# DC075B_INPUT_CLOCKS.net
KiCad netlist of a schematic drawn in Altium Designer
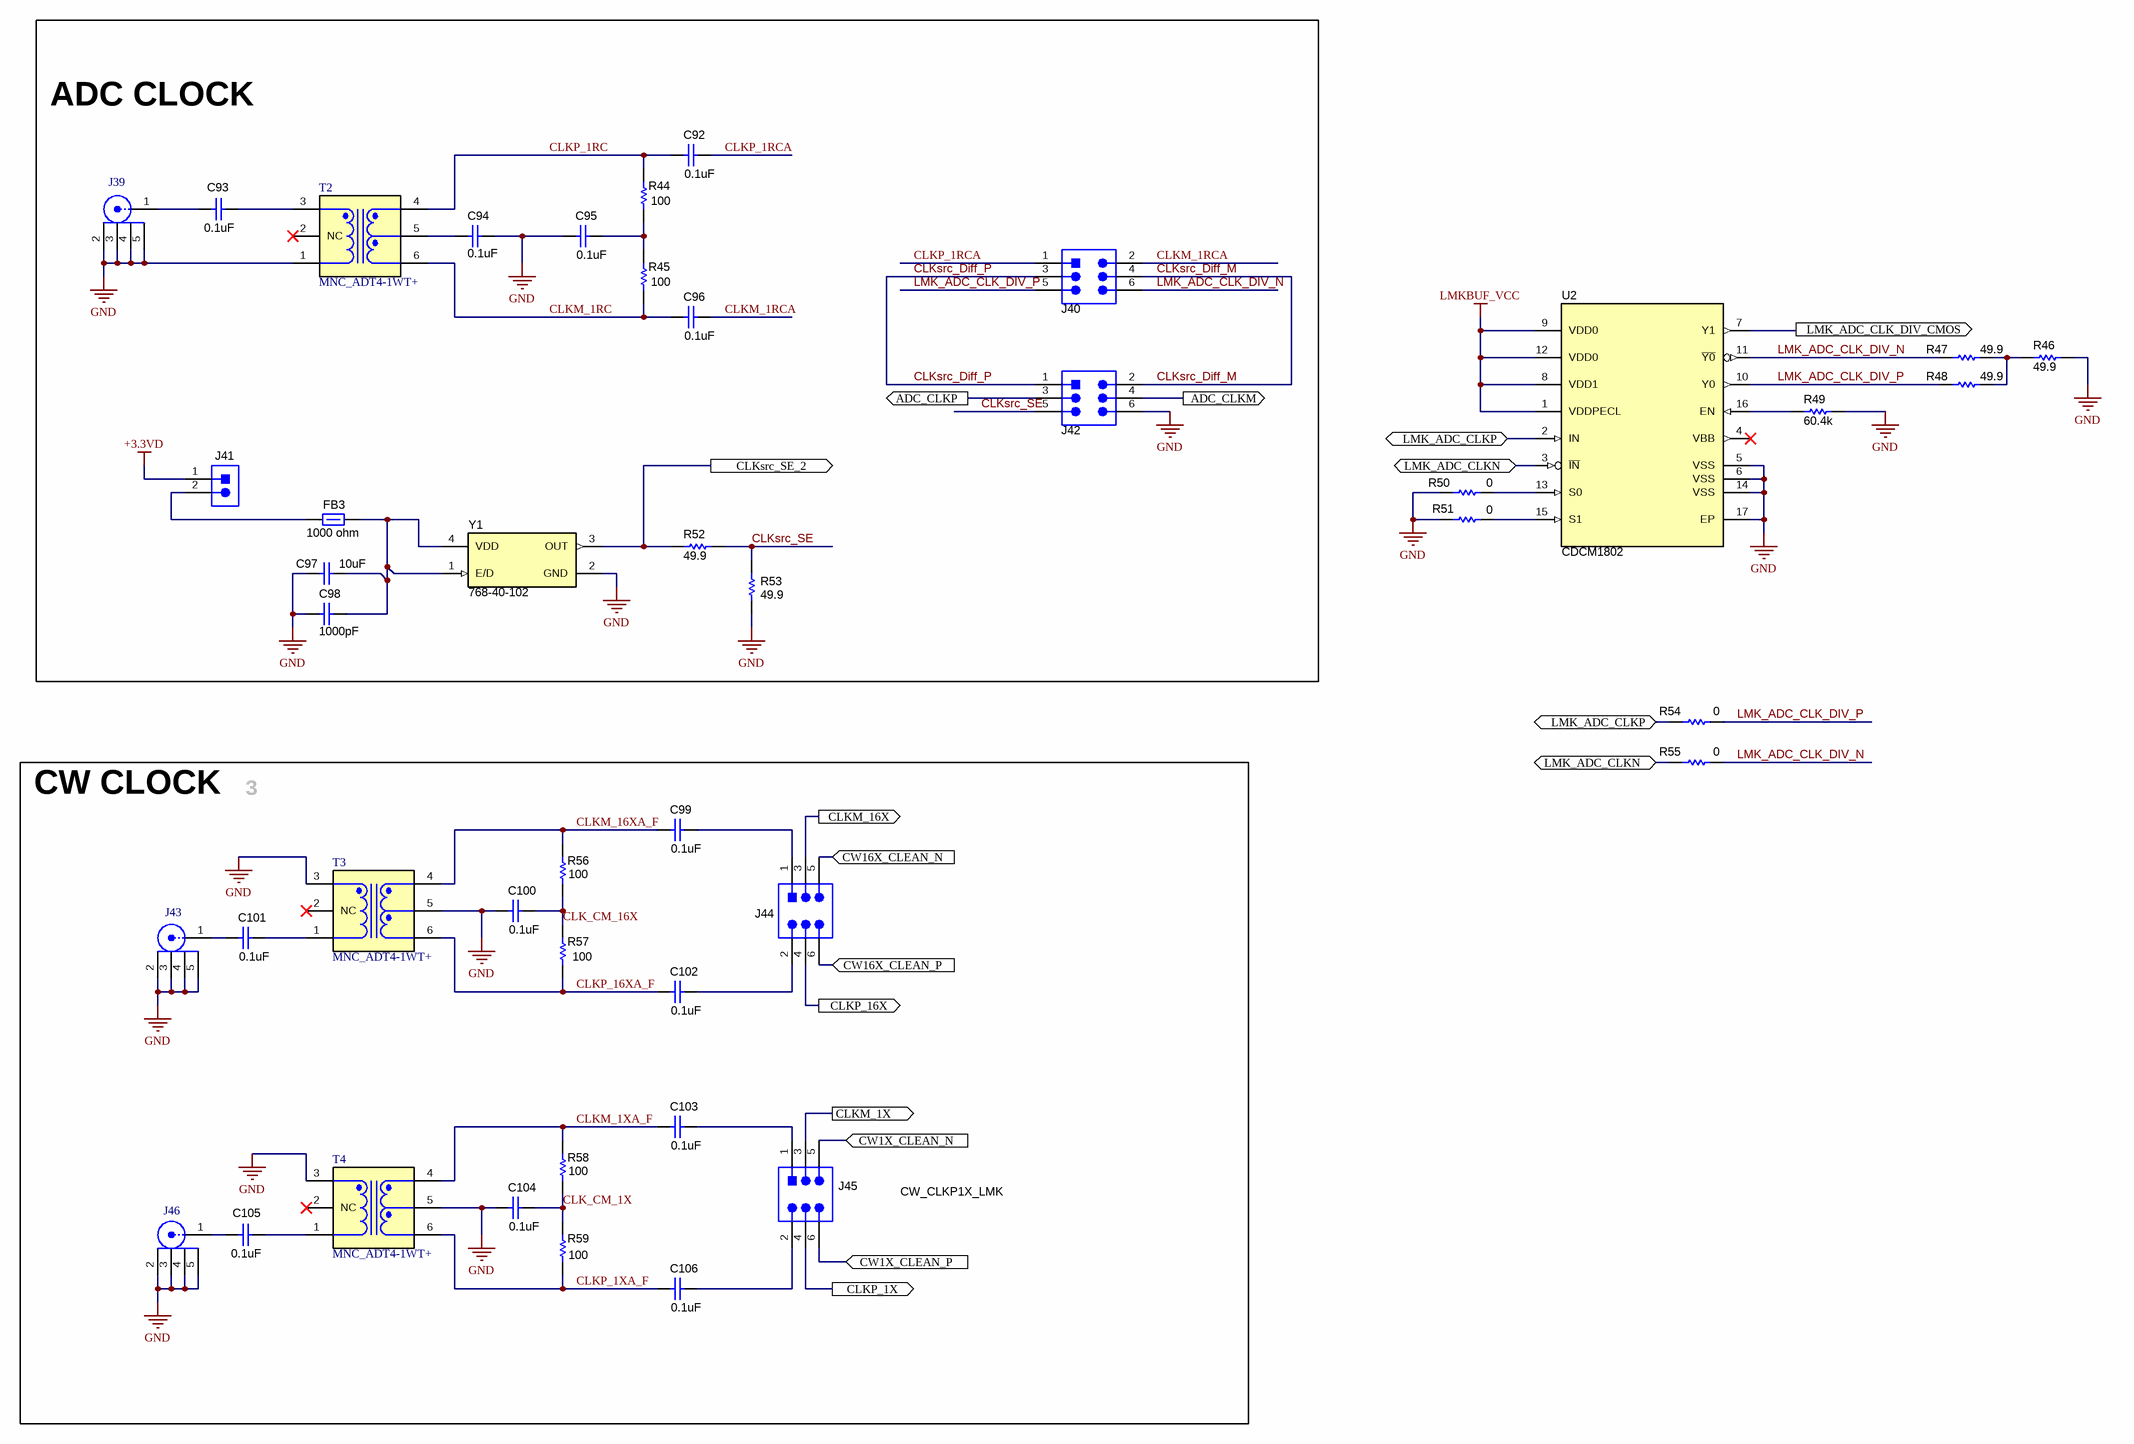
[diagram p0: DC075B_INPUT_CLOCKS.SchDoc]

(export (version "E")
  (design (tool "Eeschema 10.0.6"))
  (components
    (comp (ref "C92")
      (value "0.1uF")
      (footprint "0402")
      (description "CAP, CERM, 0.1 uF, 16 V, +/- 10%, X7R, 0402")
      (fields
        (field (name "PARTNUMBER") "GRM155R71C104KA88D")
        (field (name "MANUFACTURER") "MuRata")
        (field (name "PUBLISHER") "Texas Instruments")
      )
      (libsource (lib "Altium Vault - TI") (part "Capacitor"))
    )
    (comp (ref "C93")
      (value "0.1uF")
      (footprint "0402")
      (description "CAP, CERM, 0.1 uF, 16 V, +/- 10%, X7R, 0402")
      (fields
        (field (name "PARTNUMBER") "GRM155R71C104KA88D")
        (field (name "MANUFACTURER") "MuRata")
        (field (name "PUBLISHER") "Texas Instruments")
      )
      (libsource (lib "Altium Vault - TI") (part "Capacitor"))
    )
    (comp (ref "C94")
      (value "0.1uF")
      (footprint "0402")
      (description "CAP, CERM, 0.1 uF, 16 V, +/- 10%, X7R, 0402")
      (fields
        (field (name "PARTNUMBER") "GRM155R71C104KA88D")
        (field (name "MANUFACTURER") "MuRata")
        (field (name "PUBLISHER") "Texas Instruments")
      )
      (libsource (lib "Altium Vault - TI") (part "Capacitor"))
    )
    (comp (ref "C95")
      (value "0.1uF")
      (footprint "0402")
      (description "CAP, CERM, 0.1 uF, 16 V, +/- 10%, X7R, 0402")
      (fields
        (field (name "PARTNUMBER") "GRM155R71C104KA88D")
        (field (name "MANUFACTURER") "MuRata")
        (field (name "PUBLISHER") "Texas Instruments")
      )
      (libsource (lib "Altium Vault - TI") (part "Capacitor"))
    )
    (comp (ref "C96")
      (value "0.1uF")
      (footprint "0402")
      (description "CAP, CERM, 0.1 uF, 16 V, +/- 10%, X7R, 0402")
      (fields
        (field (name "PARTNUMBER") "GRM155R71C104KA88D")
        (field (name "MANUFACTURER") "MuRata")
        (field (name "PUBLISHER") "Texas Instruments")
      )
      (libsource (lib "Altium Vault - TI") (part "Capacitor"))
    )
    (comp (ref "C97")
      (value "10uF")
      (footprint "0603_HV")
      (description "CAP, CERM, 10 uF, 6.3 V, +/- 20%, X5R, 0603")
      (fields
        (field (name "PARTNUMBER") "C0603C106M9PACTU")
        (field (name "MANUFACTURER") "Kemet")
        (field (name "PUBLISHER") "Texas Instruments")
      )
      (libsource (lib "Altium Vault - TI") (part "Capacitor"))
    )
    (comp (ref "C98")
      (value "885012205044")
      (footprint "0402")
      (description "CAP, CERM, 1000 pF, 25 V, +/- 10%, X7R, 0402")
      (fields
        (field (name "MANUFACTURER") "Wurth Elektronik")
        (field (name "VALUEDISPLAYED") "1000pF")
        (field (name "PUBLISHER") "Texas Instruments")
      )
      (libsource (lib "Altium Vault - TI") (part "CMP-0006229-2"))
    )
    (comp (ref "C99")
      (value "0.1uF")
      (footprint "0402")
      (description "CAP, CERM, 0.1 uF, 16 V, +/- 10%, X7R, 0402")
      (fields
        (field (name "PARTNUMBER") "GRM155R71C104KA88D")
        (field (name "MANUFACTURER") "MuRata")
        (field (name "PUBLISHER") "Texas Instruments")
      )
      (libsource (lib "Altium Vault - TI") (part "Capacitor"))
    )
    (comp (ref "C100")
      (value "0.1uF")
      (footprint "0402")
      (description "CAP, CERM, 0.1 uF, 16 V, +/- 10%, X7R, 0402")
      (fields
        (field (name "PARTNUMBER") "GRM155R71C104KA88D")
        (field (name "MANUFACTURER") "MuRata")
        (field (name "PUBLISHER") "Texas Instruments")
      )
      (libsource (lib "Altium Vault - TI") (part "Capacitor"))
    )
    (comp (ref "C101")
      (value "0.1uF")
      (footprint "0402")
      (description "CAP, CERM, 0.1 uF, 16 V, +/- 10%, X7R, 0402")
      (fields
        (field (name "PARTNUMBER") "GRM155R71C104KA88D")
        (field (name "MANUFACTURER") "MuRata")
        (field (name "PUBLISHER") "Texas Instruments")
      )
      (libsource (lib "Altium Vault - TI") (part "Capacitor"))
    )
    (comp (ref "C102")
      (value "0.1uF")
      (footprint "0402")
      (description "CAP, CERM, 0.1 uF, 16 V, +/- 10%, X7R, 0402")
      (fields
        (field (name "PARTNUMBER") "GRM155R71C104KA88D")
        (field (name "MANUFACTURER") "MuRata")
        (field (name "PUBLISHER") "Texas Instruments")
      )
      (libsource (lib "Altium Vault - TI") (part "Capacitor"))
    )
    (comp (ref "C103")
      (value "0.1uF")
      (footprint "0402")
      (description "CAP, CERM, 0.1 uF, 16 V, +/- 10%, X7R, 0402")
      (fields
        (field (name "PARTNUMBER") "GRM155R71C104KA88D")
        (field (name "MANUFACTURER") "MuRata")
        (field (name "PUBLISHER") "Texas Instruments")
      )
      (libsource (lib "Altium Vault - TI") (part "Capacitor"))
    )
    (comp (ref "C104")
      (value "0.1uF")
      (footprint "0402")
      (description "CAP, CERM, 0.1 uF, 16 V, +/- 10%, X7R, 0402")
      (fields
        (field (name "PARTNUMBER") "GRM155R71C104KA88D")
        (field (name "MANUFACTURER") "MuRata")
        (field (name "PUBLISHER") "Texas Instruments")
      )
      (libsource (lib "Altium Vault - TI") (part "Capacitor"))
    )
    (comp (ref "C105")
      (value "0.1uF")
      (footprint "0402")
      (description "CAP, CERM, 0.1 uF, 16 V, +/- 10%, X7R, 0402")
      (fields
        (field (name "PARTNUMBER") "GRM155R71C104KA88D")
        (field (name "MANUFACTURER") "MuRata")
        (field (name "PUBLISHER") "Texas Instruments")
      )
      (libsource (lib "Altium Vault - TI") (part "Capacitor"))
    )
    (comp (ref "C106")
      (value "0.1uF")
      (footprint "0402")
      (description "CAP, CERM, 0.1 uF, 16 V, +/- 10%, X7R, 0402")
      (fields
        (field (name "PARTNUMBER") "GRM155R71C104KA88D")
        (field (name "MANUFACTURER") "MuRata")
        (field (name "PUBLISHER") "Texas Instruments")
      )
      (libsource (lib "Altium Vault - TI") (part "Capacitor"))
    )
    (comp (ref "FB3")
      (value "1000 ohm")
      (footprint "0402")
      (description "Ferrite Bead, 1000 ohm @ 100 MHz, 0.3 A, 0402")
      (fields
        (field (name "PARTNUMBER") "BLM15AG102SN1D")
        (field (name "MANUFACTURER") "MuRata")
        (field (name "PUBLISHER") "Texas Instruments")
      )
      (libsource (lib "Altium Vault - TI") (part "Ferrite_Bead"))
    )
    (comp (ref "J39")
      (value "5-1814832-1")
      (footprint "TE_5-1814832-1")
      (description "SMA Straight PCB Socket Die Cast, 50 Ohm, TH")
      (fields (field (name "MANUFACTURER") "TE Connectivity") (field (name "PUBLISHER") "Texas Instruments"))
      (libsource (lib "Altium Vault - TI") (part "SMA_Contact1_GND2345"))
    )
    (comp (ref "J40")
      (value "Header_3x2")
      (footprint "TSW-103-07-G-D")
      (description "Header, 100mil, 3x2, Gold, TH")
      (fields (field (name "PARTNUMBER") "TSW-103-07-G-D") (field (name "MANUFACTURER") "Samtec"))
      (libsource (lib "Altium Vault - TI") (part "Header_3x2"))
    )
    (comp (ref "J41")
      (value "Header_2x1")
      (footprint "TSW-102-07-G-S")
      (description "Header, 100mil, 2x1, Gold, TH")
      (fields (field (name "PARTNUMBER") "TSW-102-07-G-S") (field (name "MANUFACTURER") "Samtec"))
      (libsource (lib "Altium Vault - TI") (part "Header_2x1"))
    )
    (comp (ref "J42")
      (value "Header_3x2")
      (footprint "TSW-103-07-G-D")
      (description "Header, 100mil, 3x2, Gold, TH")
      (fields (field (name "PARTNUMBER") "TSW-103-07-G-D") (field (name "MANUFACTURER") "Samtec"))
      (libsource (lib "Altium Vault - TI") (part "Header_3x2"))
    )
    (comp (ref "J43")
      (value "5-1814832-1")
      (footprint "TE_5-1814832-1")
      (description "SMA Straight PCB Socket Die Cast, 50 Ohm, TH")
      (fields (field (name "MANUFACTURER") "TE Connectivity") (field (name "PUBLISHER") "Texas Instruments"))
      (libsource (lib "Altium Vault - TI") (part "SMA_Contact1_GND2345"))
    )
    (comp (ref "J44")
      (value "Header_3x2")
      (footprint "TSW-103-07-G-D")
      (description "Header, 100mil, 3x2, Gold, TH")
      (fields (field (name "PARTNUMBER") "TSW-103-07-G-D") (field (name "MANUFACTURER") "Samtec"))
      (libsource (lib "") (part "Header_3x2_1"))
    )
    (comp (ref "J45")
      (value "Header_3x2")
      (footprint "TSW-103-07-G-D")
      (description "Header, 100mil, 3x2, Gold, TH")
      (fields (field (name "PARTNUMBER") "TSW-103-07-G-D") (field (name "MANUFACTURER") "Samtec"))
      (libsource (lib "") (part "Header_3x2_1"))
    )
    (comp (ref "J46")
      (value "5-1814832-1")
      (footprint "TE_5-1814832-1")
      (description "SMA Straight PCB Socket Die Cast, 50 Ohm, TH")
      (fields (field (name "MANUFACTURER") "TE Connectivity") (field (name "PUBLISHER") "Texas Instruments"))
      (libsource (lib "Altium Vault - TI") (part "SMA_Contact1_GND2345"))
    )
    (comp (ref "R44")
      (value "Resistor")
      (footprint "0402")
      (description "RES, 100, 1%, 0.1 W, 0402")
      (fields
        (field (name "MANUFACTURER") "Panasonic")
        (field (name "PARTNUMBER") "ERJ-2RKF1000X")
        (field (name "VALUEDISPLAYED") "100")
        (field (name "PUBLISHER") "Texas Instruments")
      )
      (libsource (lib "Altium Vault - TI") (part "Resistor"))
    )
    (comp (ref "R45")
      (value "Resistor")
      (footprint "0402")
      (description "RES, 100, 1%, 0.1 W, 0402")
      (fields
        (field (name "MANUFACTURER") "Panasonic")
        (field (name "PARTNUMBER") "ERJ-2RKF1000X")
        (field (name "VALUEDISPLAYED") "100")
        (field (name "PUBLISHER") "Texas Instruments")
      )
      (libsource (lib "Altium Vault - TI") (part "Resistor"))
    )
    (comp (ref "R46")
      (value "49.9")
      (footprint "0402")
      (description "RES, 49.9, 1%, 0.063 W, AEC-Q200 Grade 0, 0402")
      (fields (field (name "MANUFACTURER") "Vishay-Dale") (field (name "PARTNUMBER") "CRCW040249R9FKED"))
      (libsource (lib "Altium Vault - TI") (part "Resistor"))
    )
    (comp (ref "R47")
      (value "49.9")
      (footprint "0402")
      (description "RES, 49.9, 1%, 0.063 W, AEC-Q200 Grade 0, 0402")
      (fields (field (name "MANUFACTURER") "Vishay-Dale") (field (name "PARTNUMBER") "CRCW040249R9FKED"))
      (libsource (lib "Altium Vault - TI") (part "Resistor"))
    )
    (comp (ref "R48")
      (value "49.9")
      (footprint "0402")
      (description "RES, 49.9, 1%, 0.063 W, AEC-Q200 Grade 0, 0402")
      (fields (field (name "MANUFACTURER") "Vishay-Dale") (field (name "PARTNUMBER") "CRCW040249R9FKED"))
      (libsource (lib "Altium Vault - TI") (part "Resistor"))
    )
    (comp (ref "R49")
      (value "60.4k")
      (footprint "0402")
      (description "RES, 60.4 k, 1%, 0.063 W, AEC-Q200 Grade 0, 0402")
      (fields (field (name "PARTNUMBER") "CRCW040260K4FKED") (field (name "MANUFACTURER") "Vishay-Dale"))
      (libsource (lib "Altium Vault - TI") (part "Resistor"))
    )
    (comp (ref "R50")
      (value "0")
      (footprint "0402")
      (description "RES, 0, 5%, 0.063 W, AEC-Q200 Grade 0, 0402")
      (fields (field (name "MANUFACTURER") "Vishay-Dale") (field (name "PARTNUMBER") "CRCW04020000Z0ED"))
      (libsource (lib "Altium Vault - TI") (part "Resistor"))
    )
    (comp (ref "R51")
      (value "0")
      (footprint "0402")
      (description "RES, 0, 5%, 0.063 W, AEC-Q200 Grade 0, 0402")
      (fields (field (name "MANUFACTURER") "Vishay-Dale") (field (name "PARTNUMBER") "CRCW04020000Z0ED"))
      (libsource (lib "Altium Vault - TI") (part "Resistor"))
    )
    (comp (ref "R52")
      (value "49.9")
      (footprint "0402")
      (description "RES, 49.9, 1%, 0.063 W, AEC-Q200 Grade 0, 0402")
      (fields (field (name "MANUFACTURER") "Vishay-Dale") (field (name "PARTNUMBER") "CRCW040249R9FKED"))
      (libsource (lib "Altium Vault - TI") (part "Resistor"))
    )
    (comp (ref "R53")
      (value "49.9")
      (footprint "0402")
      (description "RES, 49.9, 1%, 0.063 W, AEC-Q200 Grade 0, 0402")
      (fields (field (name "MANUFACTURER") "Vishay-Dale") (field (name "PARTNUMBER") "CRCW040249R9FKED"))
      (libsource (lib "Altium Vault - TI") (part "Resistor"))
    )
    (comp (ref "R54")
      (value "0")
      (footprint "0402")
      (description "RES, 0, 5%, 0.063 W, AEC-Q200 Grade 0, 0402")
      (fields (field (name "MANUFACTURER") "Vishay-Dale") (field (name "PARTNUMBER") "CRCW04020000Z0ED"))
      (libsource (lib "Altium Vault - TI") (part "Resistor"))
    )
    (comp (ref "R55")
      (value "0")
      (footprint "0402")
      (description "RES, 0, 5%, 0.063 W, AEC-Q200 Grade 0, 0402")
      (fields (field (name "MANUFACTURER") "Vishay-Dale") (field (name "PARTNUMBER") "CRCW04020000Z0ED"))
      (libsource (lib "Altium Vault - TI") (part "Resistor"))
    )
    (comp (ref "R56")
      (value "Resistor")
      (footprint "0402")
      (description "RES, 100, 1%, 0.1 W, 0402")
      (fields
        (field (name "MANUFACTURER") "Panasonic")
        (field (name "PARTNUMBER") "ERJ-2RKF1000X")
        (field (name "VALUEDISPLAYED") "100")
        (field (name "PUBLISHER") "Texas Instruments")
      )
      (libsource (lib "Altium Vault - TI") (part "Resistor"))
    )
    (comp (ref "R57")
      (value "Resistor")
      (footprint "0402")
      (description "RES, 100, 1%, 0.1 W, 0402")
      (fields
        (field (name "MANUFACTURER") "Panasonic")
        (field (name "PARTNUMBER") "ERJ-2RKF1000X")
        (field (name "VALUEDISPLAYED") "100")
        (field (name "PUBLISHER") "Texas Instruments")
      )
      (libsource (lib "Altium Vault - TI") (part "Resistor"))
    )
    (comp (ref "R58")
      (value "Resistor")
      (footprint "0402")
      (description "RES, 100, 1%, 0.1 W, 0402")
      (fields
        (field (name "MANUFACTURER") "Panasonic")
        (field (name "PARTNUMBER") "ERJ-2RKF1000X")
        (field (name "VALUEDISPLAYED") "100")
        (field (name "PUBLISHER") "Texas Instruments")
      )
      (libsource (lib "Altium Vault - TI") (part "Resistor"))
    )
    (comp (ref "R59")
      (value "Resistor")
      (footprint "0402")
      (description "RES, 100, 1%, 0.1 W, 0402")
      (fields
        (field (name "MANUFACTURER") "Panasonic")
        (field (name "PARTNUMBER") "ERJ-2RKF1000X")
        (field (name "VALUEDISPLAYED") "100")
        (field (name "PUBLISHER") "Texas Instruments")
      )
      (libsource (lib "Altium Vault - TI") (part "Resistor"))
    )
    (comp (ref "T2")
      (value "MNC_ADT4-1WT+")
      (footprint "MNC_CD542")
      (description "RF Transformer, 50 ohm, 2 to 775 MHz, SMT")
      (fields
        (field (name "PARTNUMBER") "ADT4-1WT+")
        (field (name "MANUFACTURER") "Minicircuits")
        (field (name "PUBLISHER") "Texas Instruments")
      )
      (libsource (lib "Altium Vault - TI") (part "MNC_ADT4-1WT+"))
    )
    (comp (ref "T3")
      (value "MNC_ADT4-1WT+")
      (footprint "MNC_CD542")
      (description "RF Transformer, 50 ohm, 2 to 775 MHz, SMT")
      (fields
        (field (name "PARTNUMBER") "ADT4-1WT+")
        (field (name "MANUFACTURER") "Minicircuits")
        (field (name "PUBLISHER") "Texas Instruments")
      )
      (libsource (lib "Altium Vault - TI") (part "MNC_ADT4-1WT+"))
    )
    (comp (ref "T4")
      (value "MNC_ADT4-1WT+")
      (footprint "MNC_CD542")
      (description "RF Transformer, 50 ohm, 2 to 775 MHz, SMT")
      (fields
        (field (name "PARTNUMBER") "ADT4-1WT+")
        (field (name "MANUFACTURER") "Minicircuits")
        (field (name "PUBLISHER") "Texas Instruments")
      )
      (libsource (lib "Altium Vault - TI") (part "MNC_ADT4-1WT+"))
    )
    (comp (ref "U2")
      (value "CDCM1802")
      (footprint "RGT0016A")
      (description "Clock Buffer w/Programmable Divider, LVPECL I/O + addl LVCMOS output, RGT0016A (VQFN-16)")
      (fields
        (field (name "PARTNUMBER") "CDCM1802RGTR")
        (field (name "ALTERNATE PARTNUMBER") "CDCM1802RGTT")
        (field (name "PUBLISHER") "Texas Instruments")
      )
      (libsource (lib "Altium Vault - TI") (part "CDCM1802"))
    )
    (comp (ref "Y1")
      (value "768-40-102")
      (footprint "FOX_FXO-HC73")
      (description "Crystal, 40 MHz, SMD")
      (fields (field (name "MANUFACTURER") "Fox Electronics"))
      (libsource (lib "Altium Vault - TI") (part "OSC_4P_ED"))
    )
  )
  (nets
    (net (code "1") (name "+3.3VD") (class "Default")
      (node (ref "J41") (pin "1") (pinfunction "1_1") (pintype "passive"))
    )
    (net (code "2") (name "/ADC_CLKM") (class "Default")
      (node (ref "J42") (pin "4") (pinfunction "4_4") (pintype "passive"))
    )
    (net (code "3") (name "/ADC_CLKP") (class "Default")
      (node (ref "J42") (pin "3") (pinfunction "3_3") (pintype "passive"))
    )
    (net (code "4") (name "/CLKM_1RC") (class "Default")
      (node (ref "C96") (pin "2") (pinfunction "2_2") (pintype "passive"))
      (node (ref "R45") (pin "2") (pinfunction "2_2") (pintype "passive"))
      (node (ref "T2") (pin "6") (pinfunction "6_6") (pintype "power_in"))
    )
    (net (code "5") (name "/CLKM_1RCA") (class "Default")
      (node (ref "C96") (pin "1") (pinfunction "1_1") (pintype "passive"))
      (node (ref "J40") (pin "2") (pinfunction "2_2") (pintype "passive"))
    )
    (net (code "6") (name "/CLKM_1X") (class "Default")
      (node (ref "J45") (pin "3") (pinfunction "3_3") (pintype "passive"))
    )
    (net (code "7") (name "/CLKM_1XA_F") (class "Default")
      (node (ref "C103") (pin "2") (pinfunction "2_2") (pintype "passive"))
      (node (ref "R58") (pin "2") (pinfunction "2_2") (pintype "passive"))
      (node (ref "T4") (pin "4") (pinfunction "4_4") (pintype "power_in"))
    )
    (net (code "8") (name "/CLKM_16X") (class "Default")
      (node (ref "J44") (pin "3") (pinfunction "3_3") (pintype "passive"))
    )
    (net (code "9") (name "/CLKM_16XA_F") (class "Default")
      (node (ref "C99") (pin "2") (pinfunction "2_2") (pintype "passive"))
      (node (ref "R56") (pin "2") (pinfunction "2_2") (pintype "passive"))
      (node (ref "T3") (pin "4") (pinfunction "4_4") (pintype "power_in"))
    )
    (net (code "10") (name "/CLKP_1RC") (class "Default")
      (node (ref "C92") (pin "2") (pinfunction "2_2") (pintype "passive"))
      (node (ref "R44") (pin "1") (pinfunction "1_1") (pintype "passive"))
      (node (ref "T2") (pin "4") (pinfunction "4_4") (pintype "power_in"))
    )
    (net (code "11") (name "/CLKP_1RCA") (class "Default")
      (node (ref "C92") (pin "1") (pinfunction "1_1") (pintype "passive"))
      (node (ref "J40") (pin "1") (pinfunction "1_1") (pintype "passive"))
    )
    (net (code "12") (name "/CLKP_1X") (class "Default")
      (node (ref "J45") (pin "4") (pinfunction "4_4") (pintype "passive"))
    )
    (net (code "13") (name "/CLKP_1XA_F") (class "Default")
      (node (ref "C106") (pin "2") (pinfunction "2_2") (pintype "passive"))
      (node (ref "R59") (pin "1") (pinfunction "1_1") (pintype "passive"))
      (node (ref "T4") (pin "6") (pinfunction "6_6") (pintype "power_in"))
    )
    (net (code "14") (name "/CLKP_16X") (class "Default")
      (node (ref "J44") (pin "4") (pinfunction "4_4") (pintype "passive"))
    )
    (net (code "15") (name "/CLKP_16XA_F") (class "Default")
      (node (ref "C102") (pin "2") (pinfunction "2_2") (pintype "passive"))
      (node (ref "R57") (pin "1") (pinfunction "1_1") (pintype "passive"))
      (node (ref "T3") (pin "6") (pinfunction "6_6") (pintype "power_in"))
    )
    (net (code "16") (name "/CLK_CM_1X") (class "Default")
      (node (ref "C104") (pin "1") (pinfunction "1_1") (pintype "passive"))
      (node (ref "R58") (pin "1") (pinfunction "1_1") (pintype "passive"))
      (node (ref "R59") (pin "2") (pinfunction "2_2") (pintype "passive"))
    )
    (net (code "17") (name "/CLK_CM_16X") (class "Default")
      (node (ref "C100") (pin "1") (pinfunction "1_1") (pintype "passive"))
      (node (ref "R56") (pin "1") (pinfunction "1_1") (pintype "passive"))
      (node (ref "R57") (pin "2") (pinfunction "2_2") (pintype "passive"))
    )
    (net (code "18") (name "/CLKsrc_Diff_M") (class "Default")
      (node (ref "J40") (pin "4") (pinfunction "4_4") (pintype "passive"))
      (node (ref "J42") (pin "2") (pinfunction "2_2") (pintype "passive"))
    )
    (net (code "19") (name "/CLKsrc_Diff_P") (class "Default")
      (node (ref "J40") (pin "3") (pinfunction "3_3") (pintype "passive"))
      (node (ref "J42") (pin "1") (pinfunction "1_1") (pintype "passive"))
    )
    (net (code "20") (name "/CLKsrc_SE") (class "Default")
      (node (ref "J42") (pin "5") (pinfunction "5_5") (pintype "passive"))
      (node (ref "R52") (pin "2") (pinfunction "2_2") (pintype "passive"))
      (node (ref "R53") (pin "1") (pinfunction "1_1") (pintype "passive"))
    )
    (net (code "21") (name "/CLKsrc_SE_2") (class "Default")
      (node (ref "R52") (pin "1") (pinfunction "1_1") (pintype "passive"))
      (node (ref "Y1") (pin "3") (pinfunction "OUT_3") (pintype "output"))
    )
    (net (code "22") (name "/CW1X_CLEAN_N") (class "Default")
      (node (ref "J45") (pin "5") (pinfunction "5_5") (pintype "passive"))
    )
    (net (code "23") (name "/CW1X_CLEAN_P") (class "Default")
      (node (ref "J45") (pin "6") (pinfunction "6_6") (pintype "passive"))
    )
    (net (code "24") (name "/CW16X_CLEAN_N") (class "Default")
      (node (ref "J44") (pin "5") (pinfunction "5_5") (pintype "passive"))
    )
    (net (code "25") (name "/CW16X_CLEAN_P") (class "Default")
      (node (ref "J44") (pin "6") (pinfunction "6_6") (pintype "passive"))
    )
    (net (code "26") (name "/LMK_ADC_CLKN") (class "Default")
      (node (ref "R55") (pin "2") (pinfunction "2_2") (pintype "passive"))
      (node (ref "U2") (pin "3") (pinfunction "IN_3") (pintype "input"))
    )
    (net (code "27") (name "/LMK_ADC_CLKP") (class "Default")
      (node (ref "R54") (pin "2") (pinfunction "2_2") (pintype "passive"))
      (node (ref "U2") (pin "2") (pinfunction "IN_2") (pintype "input"))
    )
    (net (code "28") (name "/LMK_ADC_CLK_DIV_CMOS") (class "Default")
      (node (ref "U2") (pin "7") (pinfunction "Y1_7") (pintype "output"))
    )
    (net (code "29") (name "/LMK_ADC_CLK_DIV_N") (class "Default")
      (node (ref "J40") (pin "6") (pinfunction "6_6") (pintype "passive"))
      (node (ref "R47") (pin "2") (pinfunction "2_2") (pintype "passive"))
      (node (ref "R55") (pin "1") (pinfunction "1_1") (pintype "passive"))
      (node (ref "U2") (pin "11") (pinfunction "Y0_11") (pintype "output"))
    )
    (net (code "30") (name "/LMK_ADC_CLK_DIV_P") (class "Default")
      (node (ref "J40") (pin "5") (pinfunction "5_5") (pintype "passive"))
      (node (ref "R48") (pin "2") (pinfunction "2_2") (pintype "passive"))
      (node (ref "R54") (pin "1") (pinfunction "1_1") (pintype "passive"))
      (node (ref "U2") (pin "10") (pinfunction "Y0_10") (pintype "output"))
    )
    (net (code "31") (name "GND") (class "Default")
      (node (ref "C100") (pin "2") (pinfunction "2_2") (pintype "passive"))
      (node (ref "C104") (pin "2") (pinfunction "2_2") (pintype "passive"))
      (node (ref "C94") (pin "2") (pinfunction "2_2") (pintype "passive"))
      (node (ref "C95") (pin "2") (pinfunction "2_2") (pintype "passive"))
      (node (ref "C97") (pin "1") (pinfunction "1_1") (pintype "passive"))
      (node (ref "C98") (pin "1") (pinfunction "1_1") (pintype "passive"))
      (node (ref "J39") (pin "2") (pinfunction "2_2") (pintype "passive"))
      (node (ref "J39") (pin "3") (pinfunction "3_3") (pintype "passive"))
      (node (ref "J39") (pin "4") (pinfunction "4_4") (pintype "passive"))
      (node (ref "J39") (pin "5") (pinfunction "5_5") (pintype "passive"))
      (node (ref "J42") (pin "6") (pinfunction "6_6") (pintype "passive"))
      (node (ref "J43") (pin "2") (pinfunction "2_2") (pintype "passive"))
      (node (ref "J43") (pin "3") (pinfunction "3_3") (pintype "passive"))
      (node (ref "J43") (pin "4") (pinfunction "4_4") (pintype "passive"))
      (node (ref "J43") (pin "5") (pinfunction "5_5") (pintype "passive"))
      (node (ref "J46") (pin "2") (pinfunction "2_2") (pintype "passive"))
      (node (ref "J46") (pin "3") (pinfunction "3_3") (pintype "passive"))
      (node (ref "J46") (pin "4") (pinfunction "4_4") (pintype "passive"))
      (node (ref "J46") (pin "5") (pinfunction "5_5") (pintype "passive"))
      (node (ref "R46") (pin "2") (pinfunction "2_2") (pintype "passive"))
      (node (ref "R49") (pin "1") (pinfunction "1_1") (pintype "passive"))
      (node (ref "R50") (pin "1") (pinfunction "1_1") (pintype "passive"))
      (node (ref "R51") (pin "1") (pinfunction "1_1") (pintype "passive"))
      (node (ref "R53") (pin "2") (pinfunction "2_2") (pintype "passive"))
      (node (ref "T2") (pin "1") (pinfunction "1_1") (pintype "power_in"))
      (node (ref "T3") (pin "3") (pinfunction "3_3") (pintype "power_in"))
      (node (ref "T3") (pin "5") (pinfunction "5_5") (pintype "power_in"))
      (node (ref "T4") (pin "3") (pinfunction "3_3") (pintype "power_in"))
      (node (ref "T4") (pin "5") (pinfunction "5_5") (pintype "power_in"))
      (node (ref "U2") (pin "14") (pinfunction "VSS_14") (pintype "power_in"))
      (node (ref "U2") (pin "17") (pinfunction "EP_17") (pintype "power_in"))
      (node (ref "U2") (pin "5") (pinfunction "VSS_5") (pintype "power_in"))
      (node (ref "U2") (pin "6") (pinfunction "VSS_6") (pintype "power_in"))
      (node (ref "Y1") (pin "2") (pinfunction "GND_2") (pintype "power_in"))
    )
    (net (code "32") (name "LMKBUF_VCC") (class "Default")
      (node (ref "U2") (pin "1") (pinfunction "VDDPECL_1") (pintype "power_in"))
      (node (ref "U2") (pin "12") (pinfunction "VDD0_12") (pintype "power_in"))
      (node (ref "U2") (pin "8") (pinfunction "VDD1_8") (pintype "power_in"))
      (node (ref "U2") (pin "9") (pinfunction "VDD0_9") (pintype "power_in"))
    )
    (net (code "33") (name "Net-(C93-Pad1)") (class "Default")
      (node (ref "C93") (pin "1") (pinfunction "1_1") (pintype "passive"))
      (node (ref "T2") (pin "3") (pinfunction "3_3") (pintype "power_in"))
    )
    (net (code "34") (name "Net-(C93-Pad2)") (class "Default")
      (node (ref "C93") (pin "2") (pinfunction "2_2") (pintype "passive"))
      (node (ref "J39") (pin "1") (pinfunction "1_1") (pintype "passive"))
    )
    (net (code "35") (name "Net-(C94-Pad1)") (class "Default")
      (node (ref "C94") (pin "1") (pinfunction "1_1") (pintype "passive"))
      (node (ref "T2") (pin "5") (pinfunction "5_5") (pintype "power_in"))
    )
    (net (code "36") (name "Net-(C95-Pad1)") (class "Default")
      (node (ref "C95") (pin "1") (pinfunction "1_1") (pintype "passive"))
      (node (ref "R44") (pin "2") (pinfunction "2_2") (pintype "passive"))
      (node (ref "R45") (pin "1") (pinfunction "1_1") (pintype "passive"))
    )
    (net (code "37") (name "Net-(C99-Pad1)") (class "Default")
      (node (ref "C99") (pin "1") (pinfunction "1_1") (pintype "passive"))
      (node (ref "J44") (pin "1") (pinfunction "1_1") (pintype "passive"))
    )
    (net (code "38") (name "Net-(C101-Pad1)") (class "Default")
      (node (ref "C101") (pin "1") (pinfunction "1_1") (pintype "passive"))
      (node (ref "T3") (pin "1") (pinfunction "1_1") (pintype "power_in"))
    )
    (net (code "39") (name "Net-(C101-Pad2)") (class "Default")
      (node (ref "C101") (pin "2") (pinfunction "2_2") (pintype "passive"))
      (node (ref "J43") (pin "1") (pinfunction "1_1") (pintype "passive"))
    )
    (net (code "40") (name "Net-(C102-Pad1)") (class "Default")
      (node (ref "C102") (pin "1") (pinfunction "1_1") (pintype "passive"))
      (node (ref "J44") (pin "2") (pinfunction "2_2") (pintype "passive"))
    )
    (net (code "41") (name "Net-(C103-Pad1)") (class "Default")
      (node (ref "C103") (pin "1") (pinfunction "1_1") (pintype "passive"))
      (node (ref "J45") (pin "1") (pinfunction "1_1") (pintype "passive"))
    )
    (net (code "42") (name "Net-(C105-Pad1)") (class "Default")
      (node (ref "C105") (pin "1") (pinfunction "1_1") (pintype "passive"))
      (node (ref "T4") (pin "1") (pinfunction "1_1") (pintype "power_in"))
    )
    (net (code "43") (name "Net-(C105-Pad2)") (class "Default")
      (node (ref "C105") (pin "2") (pinfunction "2_2") (pintype "passive"))
      (node (ref "J46") (pin "1") (pinfunction "1_1") (pintype "passive"))
    )
    (net (code "44") (name "Net-(C106-Pad1)") (class "Default")
      (node (ref "C106") (pin "1") (pinfunction "1_1") (pintype "passive"))
      (node (ref "J45") (pin "2") (pinfunction "2_2") (pintype "passive"))
    )
    (net (code "45") (name "Net-(FB3-Pad2)") (class "Default")
      (node (ref "FB3") (pin "2") (pinfunction "2_2") (pintype "passive"))
      (node (ref "J41") (pin "2") (pinfunction "2_2") (pintype "passive"))
    )
    (net (code "46") (name "Net-(R46-Pad1)") (class "Default")
      (node (ref "R46") (pin "1") (pinfunction "1_1") (pintype "passive"))
      (node (ref "R47") (pin "1") (pinfunction "1_1") (pintype "passive"))
      (node (ref "R48") (pin "1") (pinfunction "1_1") (pintype "passive"))
    )
    (net (code "47") (name "Net-(U2-EN)") (class "Default")
      (node (ref "R49") (pin "2") (pinfunction "2_2") (pintype "passive"))
      (node (ref "U2") (pin "16") (pinfunction "EN_16") (pintype "input"))
    )
    (net (code "48") (name "Net-(U2-S0)") (class "Default")
      (node (ref "R50") (pin "2") (pinfunction "2_2") (pintype "passive"))
      (node (ref "U2") (pin "13") (pinfunction "S0_13") (pintype "input"))
    )
    (net (code "49") (name "Net-(U2-S1)") (class "Default")
      (node (ref "R51") (pin "2") (pinfunction "2_2") (pintype "passive"))
      (node (ref "U2") (pin "15") (pinfunction "S1_15") (pintype "input"))
    )
    (net (code "50") (name "Net-(Y1-E{slash}D)") (class "Default")
      (node (ref "C97") (pin "2") (pinfunction "2_2") (pintype "passive"))
      (node (ref "C98") (pin "2") (pinfunction "2_2") (pintype "passive"))
      (node (ref "FB3") (pin "1") (pinfunction "1_1") (pintype "passive"))
      (node (ref "Y1") (pin "1") (pinfunction "E/D_1") (pintype "input"))
      (node (ref "Y1") (pin "4") (pinfunction "VDD_4") (pintype "power_in"))
    )
    (net (code "51") (name "unconnected-(T2-NC-Pad2)") (class "Default")
      (node (ref "T2") (pin "2") (pinfunction "NC_2") (pintype "passive+no_connect"))
    )
    (net (code "52") (name "unconnected-(T3-NC-Pad2)") (class "Default")
      (node (ref "T3") (pin "2") (pinfunction "NC_2") (pintype "passive+no_connect"))
    )
    (net (code "53") (name "unconnected-(T4-NC-Pad2)") (class "Default")
      (node (ref "T4") (pin "2") (pinfunction "NC_2") (pintype "passive+no_connect"))
    )
    (net (code "54") (name "unconnected-(U2-VBB-Pad4)") (class "Default")
      (node (ref "U2") (pin "4") (pinfunction "VBB_4") (pintype "output+no_connect"))
    )
  )
)
